# ant_system.net
KiCad netlist of a schematic drawn in Altium Designer
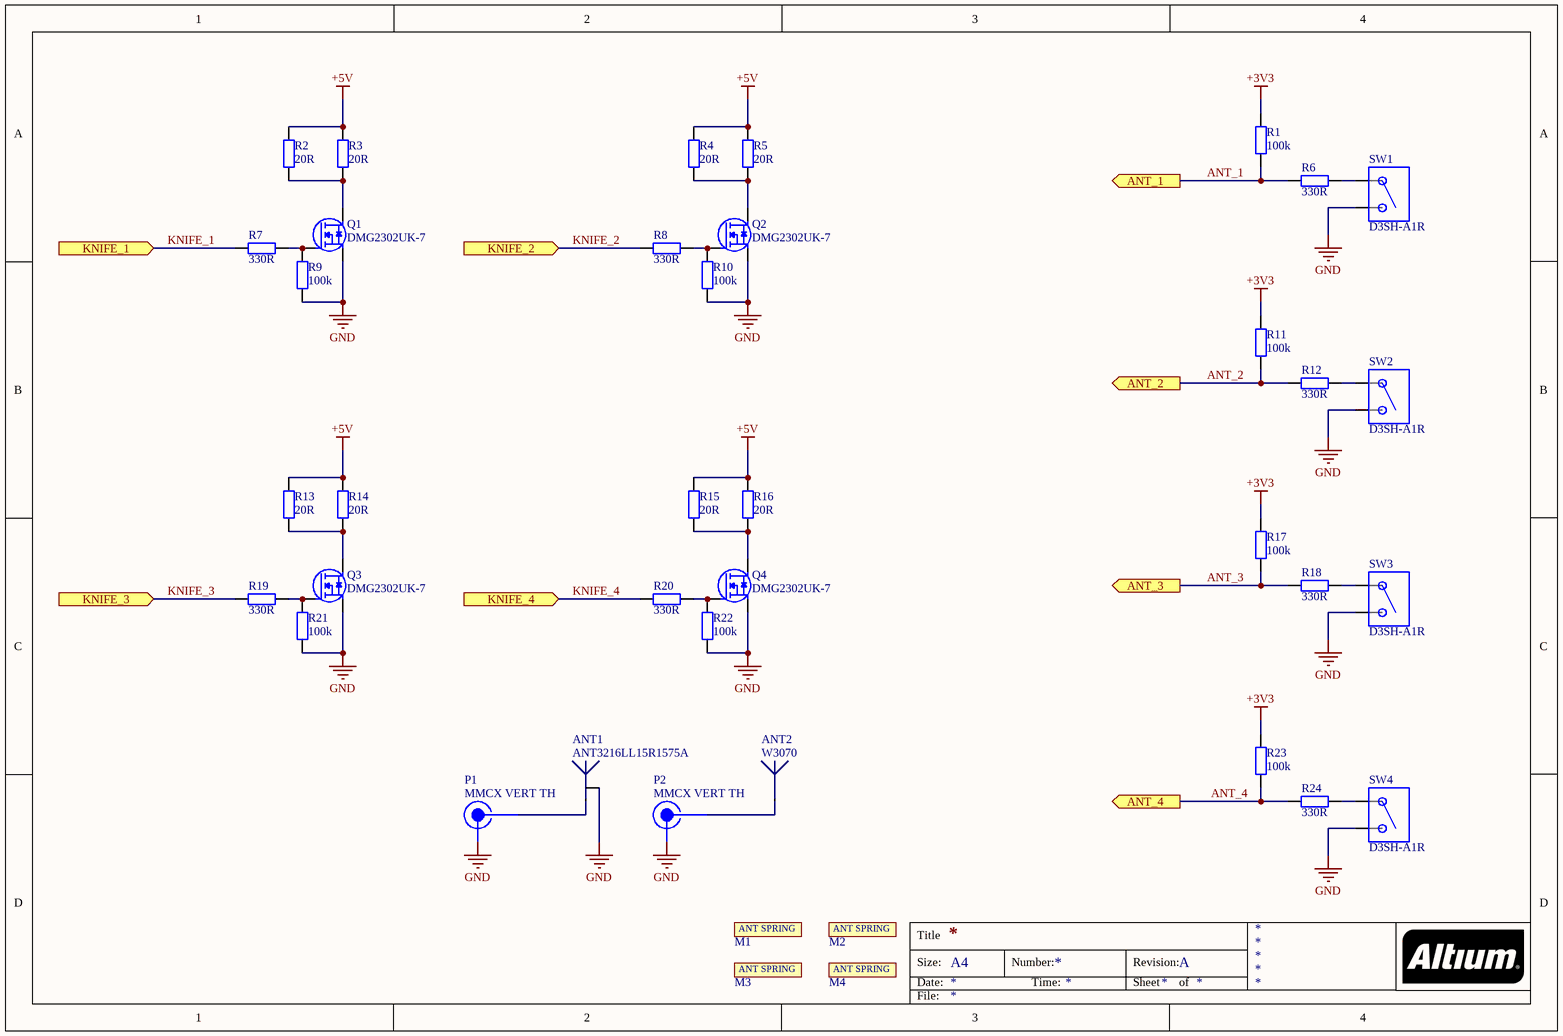
[diagram p0: ant_system.SchDoc]

(export (version "E")
  (design (tool "Eeschema 10.0.6"))
  (components
    (comp (ref "ANT1")
      (value "ANT3216LL15R1575A")
      (footprint "ANT3216LL15")
      (description "RF ANT 1.575GHZ CHIP SOLDER SMD")
      (fields (field (name "MANUFACTURER") "Yageo"))
      (libsource (lib "alfasat_lib") (part "ANT3216LL15R1575A"))
    )
    (comp (ref "ANT2")
      (value "W3070")
      (footprint "W3070")
      (description "RF ANT 900MHZ/1.8GHZ CHIP SLD")
      (fields (field (name "MANUFACTURER") "PulseLarsen Antennas"))
      (libsource (lib "alfasat_lib") (part "W3070"))
    )
    (comp (ref "M1")
      (value "*")
      (footprint "ANT_SPRING")
      (description "Antenna spring soldering pad")
      (libsource (lib "alfasat_parts_lib") (part "ANT_SPRING"))
    )
    (comp (ref "M2")
      (value "*")
      (footprint "ANT_SPRING")
      (description "Antenna spring soldering pad")
      (libsource (lib "alfasat_parts_lib") (part "ANT_SPRING"))
    )
    (comp (ref "M3")
      (value "*")
      (footprint "ANT_SPRING")
      (description "Antenna spring soldering pad")
      (libsource (lib "alfasat_parts_lib") (part "ANT_SPRING"))
    )
    (comp (ref "M4")
      (value "*")
      (footprint "ANT_SPRING")
      (description "Antenna spring soldering pad")
      (libsource (lib "alfasat_parts_lib") (part "ANT_SPRING"))
    )
    (comp (ref "P1")
      (value "MMCX VERT TH")
      (footprint "MMCX_VERT_TH")
      (description "MMCX PCB TH VERT CONN")
      (fields (field (name "MANUFACTURER") "China"))
      (libsource (lib "alfasat_lib") (part "MMCX_VERT"))
    )
    (comp (ref "P2")
      (value "MMCX VERT TH")
      (footprint "MMCX_VERT_TH")
      (description "MMCX PCB TH VERT CONN")
      (fields (field (name "MANUFACTURER") "China"))
      (libsource (lib "alfasat_lib") (part "MMCX_VERT"))
    )
    (comp (ref "Q1")
      (value "DMG2302UK-7")
      (footprint "SOT23")
      (description "N-Channel Logic Level Enhancement Mode Field Effect Transistor")
      (fields (field (name "MANUFACTURER") "Diodes Incorporated"))
      (libsource (lib "alfasat_lib") (part "DMG2302"))
    )
    (comp (ref "Q2")
      (value "DMG2302UK-7")
      (footprint "SOT23")
      (description "N-Channel Logic Level Enhancement Mode Field Effect Transistor")
      (fields (field (name "MANUFACTURER") "Diodes Incorporated"))
      (libsource (lib "alfasat_lib") (part "DMG2302"))
    )
    (comp (ref "Q3")
      (value "DMG2302UK-7")
      (footprint "SOT23")
      (description "N-Channel Logic Level Enhancement Mode Field Effect Transistor")
      (fields (field (name "MANUFACTURER") "Diodes Incorporated"))
      (libsource (lib "alfasat_lib") (part "DMG2302"))
    )
    (comp (ref "Q4")
      (value "DMG2302UK-7")
      (footprint "SOT23")
      (description "N-Channel Logic Level Enhancement Mode Field Effect Transistor")
      (fields (field (name "MANUFACTURER") "Diodes Incorporated"))
      (libsource (lib "alfasat_lib") (part "DMG2302"))
    )
    (comp (ref "R1")
      (value "100k")
      (footprint "R0603_IPC_MD")
      (description "RES 100K OHM 1% 1/10W 0603")
      (fields
        (field (name "MANUFACTURER") "Bourns Inc.")
        (field (name "MANUFACTURER PART NUMBER") "RMCF0603FT100K")
      )
      (libsource (lib "alfasat_lib") (part "RMCF0603FT100K"))
    )
    (comp (ref "R2")
      (value "20R")
      (footprint "R0805_IPC_MD")
      (description "RES SMD 20 OHM 5% 1/8W 0805")
      (fields
        (field (name "MANUFACTURER") "Yageo")
        (field (name "MANUFACTURER PART NUMBER") "RC0805JR-0720RL")
      )
      (libsource (lib "alfasat_lib") (part "RC0805JR-0720RL"))
    )
    (comp (ref "R3")
      (value "20R")
      (footprint "R0805_IPC_MD")
      (description "RES SMD 20 OHM 5% 1/8W 0805")
      (fields
        (field (name "MANUFACTURER") "Yageo")
        (field (name "MANUFACTURER PART NUMBER") "RC0805JR-0720RL")
      )
      (libsource (lib "alfasat_lib") (part "RC0805JR-0720RL"))
    )
    (comp (ref "R4")
      (value "20R")
      (footprint "R0805_IPC_MD")
      (description "RES SMD 20 OHM 5% 1/8W 0805")
      (fields
        (field (name "MANUFACTURER") "Yageo")
        (field (name "MANUFACTURER PART NUMBER") "RC0805JR-0720RL")
      )
      (libsource (lib "alfasat_lib") (part "RC0805JR-0720RL"))
    )
    (comp (ref "R5")
      (value "20R")
      (footprint "R0805_IPC_MD")
      (description "RES SMD 20 OHM 5% 1/8W 0805")
      (fields
        (field (name "MANUFACTURER") "Yageo")
        (field (name "MANUFACTURER PART NUMBER") "RC0805JR-0720RL")
      )
      (libsource (lib "alfasat_lib") (part "RC0805JR-0720RL"))
    )
    (comp (ref "R6")
      (value "330R")
      (footprint "R0603_IPC_MD")
      (description "RES SMD 330 OHM 5% 1/10W 0603")
      (fields
        (field (name "MANUFACTURER") "Bourns Inc.")
        (field (name "MANUFACTURER PART NUMBER") "CR0603-JW-331ELF")
      )
      (libsource (lib "alfasat_parts_lib") (part "CR0603-JW-331ELF"))
    )
    (comp (ref "R7")
      (value "330R")
      (footprint "R0603_IPC_MD")
      (description "RES SMD 330 OHM 5% 1/10W 0603")
      (fields
        (field (name "MANUFACTURER") "Bourns Inc.")
        (field (name "MANUFACTURER PART NUMBER") "CR0603-JW-331ELF")
      )
      (libsource (lib "alfasat_lib") (part "CR0603-JW-331ELF"))
    )
    (comp (ref "R8")
      (value "330R")
      (footprint "R0603_IPC_MD")
      (description "RES SMD 330 OHM 5% 1/10W 0603")
      (fields
        (field (name "MANUFACTURER") "Bourns Inc.")
        (field (name "MANUFACTURER PART NUMBER") "CR0603-JW-331ELF")
      )
      (libsource (lib "alfasat_lib") (part "CR0603-JW-331ELF"))
    )
    (comp (ref "R9")
      (value "100k")
      (footprint "R0603_IPC_MD")
      (description "RES 100K OHM 1% 1/10W 0603")
      (fields
        (field (name "MANUFACTURER") "Bourns Inc.")
        (field (name "MANUFACTURER PART NUMBER") "RMCF0603FT100K")
      )
      (libsource (lib "alfasat_lib") (part "RMCF0603FT100K"))
    )
    (comp (ref "R10")
      (value "100k")
      (footprint "R0603_IPC_MD")
      (description "RES 100K OHM 1% 1/10W 0603")
      (fields
        (field (name "MANUFACTURER") "Bourns Inc.")
        (field (name "MANUFACTURER PART NUMBER") "RMCF0603FT100K")
      )
      (libsource (lib "alfasat_lib") (part "RMCF0603FT100K"))
    )
    (comp (ref "R11")
      (value "100k")
      (footprint "R0603_IPC_MD")
      (description "RES 100K OHM 1% 1/10W 0603")
      (fields
        (field (name "MANUFACTURER") "Bourns Inc.")
        (field (name "MANUFACTURER PART NUMBER") "RMCF0603FT100K")
      )
      (libsource (lib "alfasat_lib") (part "RMCF0603FT100K"))
    )
    (comp (ref "R12")
      (value "330R")
      (footprint "R0603_IPC_MD")
      (description "RES SMD 330 OHM 5% 1/10W 0603")
      (fields
        (field (name "MANUFACTURER") "Bourns Inc.")
        (field (name "MANUFACTURER PART NUMBER") "CR0603-JW-331ELF")
      )
      (libsource (lib "alfasat_parts_lib") (part "CR0603-JW-331ELF"))
    )
    (comp (ref "R13")
      (value "20R")
      (footprint "R0805_IPC_MD")
      (description "RES SMD 20 OHM 5% 1/8W 0805")
      (fields
        (field (name "MANUFACTURER") "Yageo")
        (field (name "MANUFACTURER PART NUMBER") "RC0805JR-0720RL")
      )
      (libsource (lib "alfasat_lib") (part "RC0805JR-0720RL"))
    )
    (comp (ref "R14")
      (value "20R")
      (footprint "R0805_IPC_MD")
      (description "RES SMD 20 OHM 5% 1/8W 0805")
      (fields
        (field (name "MANUFACTURER") "Yageo")
        (field (name "MANUFACTURER PART NUMBER") "RC0805JR-0720RL")
      )
      (libsource (lib "alfasat_lib") (part "RC0805JR-0720RL"))
    )
    (comp (ref "R15")
      (value "20R")
      (footprint "R0805_IPC_MD")
      (description "RES SMD 20 OHM 5% 1/8W 0805")
      (fields
        (field (name "MANUFACTURER") "Yageo")
        (field (name "MANUFACTURER PART NUMBER") "RC0805JR-0720RL")
      )
      (libsource (lib "alfasat_lib") (part "RC0805JR-0720RL"))
    )
    (comp (ref "R16")
      (value "20R")
      (footprint "R0805_IPC_MD")
      (description "RES SMD 20 OHM 5% 1/8W 0805")
      (fields
        (field (name "MANUFACTURER") "Yageo")
        (field (name "MANUFACTURER PART NUMBER") "RC0805JR-0720RL")
      )
      (libsource (lib "alfasat_lib") (part "RC0805JR-0720RL"))
    )
    (comp (ref "R17")
      (value "100k")
      (footprint "R0603_IPC_MD")
      (description "RES 100K OHM 1% 1/10W 0603")
      (fields
        (field (name "MANUFACTURER") "Bourns Inc.")
        (field (name "MANUFACTURER PART NUMBER") "RMCF0603FT100K")
      )
      (libsource (lib "alfasat_lib") (part "RMCF0603FT100K"))
    )
    (comp (ref "R18")
      (value "330R")
      (footprint "R0603_IPC_MD")
      (description "RES SMD 330 OHM 5% 1/10W 0603")
      (fields
        (field (name "MANUFACTURER") "Bourns Inc.")
        (field (name "MANUFACTURER PART NUMBER") "CR0603-JW-331ELF")
      )
      (libsource (lib "alfasat_parts_lib") (part "CR0603-JW-331ELF"))
    )
    (comp (ref "R19")
      (value "330R")
      (footprint "R0603_IPC_MD")
      (description "RES SMD 330 OHM 5% 1/10W 0603")
      (fields
        (field (name "MANUFACTURER") "Bourns Inc.")
        (field (name "MANUFACTURER PART NUMBER") "CR0603-JW-331ELF")
      )
      (libsource (lib "alfasat_lib") (part "CR0603-JW-331ELF"))
    )
    (comp (ref "R20")
      (value "330R")
      (footprint "R0603_IPC_MD")
      (description "RES SMD 330 OHM 5% 1/10W 0603")
      (fields
        (field (name "MANUFACTURER") "Bourns Inc.")
        (field (name "MANUFACTURER PART NUMBER") "CR0603-JW-331ELF")
      )
      (libsource (lib "alfasat_lib") (part "CR0603-JW-331ELF"))
    )
    (comp (ref "R21")
      (value "100k")
      (footprint "R0603_IPC_MD")
      (description "RES 100K OHM 1% 1/10W 0603")
      (fields
        (field (name "MANUFACTURER") "Bourns Inc.")
        (field (name "MANUFACTURER PART NUMBER") "RMCF0603FT100K")
      )
      (libsource (lib "alfasat_lib") (part "RMCF0603FT100K"))
    )
    (comp (ref "R22")
      (value "100k")
      (footprint "R0603_IPC_MD")
      (description "RES 100K OHM 1% 1/10W 0603")
      (fields
        (field (name "MANUFACTURER") "Bourns Inc.")
        (field (name "MANUFACTURER PART NUMBER") "RMCF0603FT100K")
      )
      (libsource (lib "alfasat_lib") (part "RMCF0603FT100K"))
    )
    (comp (ref "R23")
      (value "100k")
      (footprint "R0603_IPC_MD")
      (description "RES 100K OHM 1% 1/10W 0603")
      (fields
        (field (name "MANUFACTURER") "Bourns Inc.")
        (field (name "MANUFACTURER PART NUMBER") "RMCF0603FT100K")
      )
      (libsource (lib "alfasat_lib") (part "RMCF0603FT100K"))
    )
    (comp (ref "R24")
      (value "330R")
      (footprint "R0603_IPC_MD")
      (description "RES SMD 330 OHM 5% 1/10W 0603")
      (fields
        (field (name "MANUFACTURER") "Bourns Inc.")
        (field (name "MANUFACTURER PART NUMBER") "CR0603-JW-331ELF")
      )
      (libsource (lib "alfasat_parts_lib") (part "CR0603-JW-331ELF"))
    )
    (comp (ref "SW1")
      (value "D3SH-A1R")
      (footprint "D3SH-A1R")
      (description "SWITCH DETECTOR SPST-NO 1MA 5V")
      (fields (field (name "MANUFACTURER") "Omron Electronics Inc-EMC Div"))
      (libsource (lib "alfasat_lib") (part "D3SH-A1R"))
    )
    (comp (ref "SW2")
      (value "D3SH-A1R")
      (footprint "D3SH-A1R")
      (description "SWITCH DETECTOR SPST-NO 1MA 5V")
      (fields (field (name "MANUFACTURER") "Omron Electronics Inc-EMC Div"))
      (libsource (lib "alfasat_lib") (part "D3SH-A1R"))
    )
    (comp (ref "SW3")
      (value "D3SH-A1R")
      (footprint "D3SH-A1R")
      (description "SWITCH DETECTOR SPST-NO 1MA 5V")
      (fields (field (name "MANUFACTURER") "Omron Electronics Inc-EMC Div"))
      (libsource (lib "alfasat_lib") (part "D3SH-A1R"))
    )
    (comp (ref "SW4")
      (value "D3SH-A1R")
      (footprint "D3SH-A1R")
      (description "SWITCH DETECTOR SPST-NO 1MA 5V")
      (fields (field (name "MANUFACTURER") "Omron Electronics Inc-EMC Div"))
      (libsource (lib "alfasat_lib") (part "D3SH-A1R"))
    )
  )
  (nets
    (net (code "1") (name "+3V3") (class "Default")
      (node (ref "R1") (pin "2") (pinfunction "2_2") (pintype "passive"))
      (node (ref "R11") (pin "2") (pinfunction "2_2") (pintype "passive"))
      (node (ref "R17") (pin "2") (pinfunction "2_2") (pintype "passive"))
      (node (ref "R23") (pin "2") (pinfunction "2_2") (pintype "passive"))
    )
    (net (code "2") (name "+5V") (class "Default")
      (node (ref "R13") (pin "2") (pinfunction "2_2") (pintype "passive"))
      (node (ref "R14") (pin "2") (pinfunction "2_2") (pintype "passive"))
      (node (ref "R15") (pin "2") (pinfunction "2_2") (pintype "passive"))
      (node (ref "R16") (pin "2") (pinfunction "2_2") (pintype "passive"))
      (node (ref "R2") (pin "2") (pinfunction "2_2") (pintype "passive"))
      (node (ref "R3") (pin "2") (pinfunction "2_2") (pintype "passive"))
      (node (ref "R4") (pin "2") (pinfunction "2_2") (pintype "passive"))
      (node (ref "R5") (pin "2") (pinfunction "2_2") (pintype "passive"))
    )
    (net (code "3") (name "/ANT_1") (class "Default")
      (node (ref "R1") (pin "1") (pinfunction "1_1") (pintype "passive"))
      (node (ref "R6") (pin "2") (pinfunction "2_2") (pintype "passive"))
    )
    (net (code "4") (name "/ANT_2") (class "Default")
      (node (ref "R11") (pin "1") (pinfunction "1_1") (pintype "passive"))
      (node (ref "R12") (pin "2") (pinfunction "2_2") (pintype "passive"))
    )
    (net (code "5") (name "/ANT_3") (class "Default")
      (node (ref "R17") (pin "1") (pinfunction "1_1") (pintype "passive"))
      (node (ref "R18") (pin "2") (pinfunction "2_2") (pintype "passive"))
    )
    (net (code "6") (name "/ANT_4") (class "Default")
      (node (ref "R23") (pin "1") (pinfunction "1_1") (pintype "passive"))
      (node (ref "R24") (pin "2") (pinfunction "2_2") (pintype "passive"))
    )
    (net (code "7") (name "/KNIFE_1") (class "Default")
      (node (ref "R7") (pin "2") (pinfunction "2_2") (pintype "passive"))
    )
    (net (code "8") (name "/KNIFE_2") (class "Default")
      (node (ref "R8") (pin "2") (pinfunction "2_2") (pintype "passive"))
    )
    (net (code "9") (name "/KNIFE_3") (class "Default")
      (node (ref "R19") (pin "2") (pinfunction "2_2") (pintype "passive"))
    )
    (net (code "10") (name "/KNIFE_4") (class "Default")
      (node (ref "R20") (pin "2") (pinfunction "2_2") (pintype "passive"))
    )
    (net (code "11") (name "GND") (class "Default")
      (node (ref "ANT1") (pin "2") (pinfunction "2_2") (pintype "passive"))
      (node (ref "P1") (pin "1") (pinfunction "1_1") (pintype "passive"))
      (node (ref "P2") (pin "1") (pinfunction "1_1") (pintype "passive"))
      (node (ref "Q1") (pin "2") (pinfunction "S_2") (pintype "passive"))
      (node (ref "Q2") (pin "2") (pinfunction "S_2") (pintype "passive"))
      (node (ref "Q3") (pin "2") (pinfunction "S_2") (pintype "passive"))
      (node (ref "Q4") (pin "2") (pinfunction "S_2") (pintype "passive"))
      (node (ref "R10") (pin "1") (pinfunction "1_1") (pintype "passive"))
      (node (ref "R21") (pin "1") (pinfunction "1_1") (pintype "passive"))
      (node (ref "R22") (pin "1") (pinfunction "1_1") (pintype "passive"))
      (node (ref "R9") (pin "1") (pinfunction "1_1") (pintype "passive"))
      (node (ref "SW1") (pin "2") (pinfunction "2_2") (pintype "passive"))
      (node (ref "SW2") (pin "2") (pinfunction "2_2") (pintype "passive"))
      (node (ref "SW3") (pin "2") (pinfunction "2_2") (pintype "passive"))
      (node (ref "SW4") (pin "2") (pinfunction "2_2") (pintype "passive"))
    )
    (net (code "12") (name "Net-(ANT1-Pad1)") (class "Default")
      (node (ref "ANT1") (pin "1") (pinfunction "1_1") (pintype "passive"))
      (node (ref "P1") (pin "2") (pinfunction "2_2") (pintype "passive"))
    )
    (net (code "13") (name "Net-(ANT2-Pad1)") (class "Default")
      (node (ref "ANT2") (pin "1") (pinfunction "1_1") (pintype "passive"))
      (node (ref "P2") (pin "2") (pinfunction "2_2") (pintype "passive"))
    )
    (net (code "14") (name "Net-(Q1-D)") (class "Default")
      (node (ref "Q1") (pin "3") (pinfunction "D_3") (pintype "passive"))
      (node (ref "R2") (pin "1") (pinfunction "1_1") (pintype "passive"))
      (node (ref "R3") (pin "1") (pinfunction "1_1") (pintype "passive"))
    )
    (net (code "15") (name "Net-(Q1-G)") (class "Default")
      (node (ref "Q1") (pin "1") (pinfunction "G_1") (pintype "passive"))
      (node (ref "R7") (pin "1") (pinfunction "1_1") (pintype "passive"))
      (node (ref "R9") (pin "2") (pinfunction "2_2") (pintype "passive"))
    )
    (net (code "16") (name "Net-(Q2-D)") (class "Default")
      (node (ref "Q2") (pin "3") (pinfunction "D_3") (pintype "passive"))
      (node (ref "R4") (pin "1") (pinfunction "1_1") (pintype "passive"))
      (node (ref "R5") (pin "1") (pinfunction "1_1") (pintype "passive"))
    )
    (net (code "17") (name "Net-(Q2-G)") (class "Default")
      (node (ref "Q2") (pin "1") (pinfunction "G_1") (pintype "passive"))
      (node (ref "R10") (pin "2") (pinfunction "2_2") (pintype "passive"))
      (node (ref "R8") (pin "1") (pinfunction "1_1") (pintype "passive"))
    )
    (net (code "18") (name "Net-(Q3-D)") (class "Default")
      (node (ref "Q3") (pin "3") (pinfunction "D_3") (pintype "passive"))
      (node (ref "R13") (pin "1") (pinfunction "1_1") (pintype "passive"))
      (node (ref "R14") (pin "1") (pinfunction "1_1") (pintype "passive"))
    )
    (net (code "19") (name "Net-(Q3-G)") (class "Default")
      (node (ref "Q3") (pin "1") (pinfunction "G_1") (pintype "passive"))
      (node (ref "R19") (pin "1") (pinfunction "1_1") (pintype "passive"))
      (node (ref "R21") (pin "2") (pinfunction "2_2") (pintype "passive"))
    )
    (net (code "20") (name "Net-(Q4-D)") (class "Default")
      (node (ref "Q4") (pin "3") (pinfunction "D_3") (pintype "passive"))
      (node (ref "R15") (pin "1") (pinfunction "1_1") (pintype "passive"))
      (node (ref "R16") (pin "1") (pinfunction "1_1") (pintype "passive"))
    )
    (net (code "21") (name "Net-(Q4-G)") (class "Default")
      (node (ref "Q4") (pin "1") (pinfunction "G_1") (pintype "passive"))
      (node (ref "R20") (pin "1") (pinfunction "1_1") (pintype "passive"))
      (node (ref "R22") (pin "2") (pinfunction "2_2") (pintype "passive"))
    )
    (net (code "22") (name "Net-(R6-Pad1)") (class "Default")
      (node (ref "R6") (pin "1") (pinfunction "1_1") (pintype "passive"))
      (node (ref "SW1") (pin "1") (pinfunction "1_1") (pintype "passive"))
    )
    (net (code "23") (name "Net-(R12-Pad1)") (class "Default")
      (node (ref "R12") (pin "1") (pinfunction "1_1") (pintype "passive"))
      (node (ref "SW2") (pin "1") (pinfunction "1_1") (pintype "passive"))
    )
    (net (code "24") (name "Net-(R18-Pad1)") (class "Default")
      (node (ref "R18") (pin "1") (pinfunction "1_1") (pintype "passive"))
      (node (ref "SW3") (pin "1") (pinfunction "1_1") (pintype "passive"))
    )
    (net (code "25") (name "Net-(R24-Pad1)") (class "Default")
      (node (ref "R24") (pin "1") (pinfunction "1_1") (pintype "passive"))
      (node (ref "SW4") (pin "1") (pinfunction "1_1") (pintype "passive"))
    )
  )
)
